# DIY_DAP_PCB_Audio.net
KiCad netlist of a schematic drawn in Altium Designer
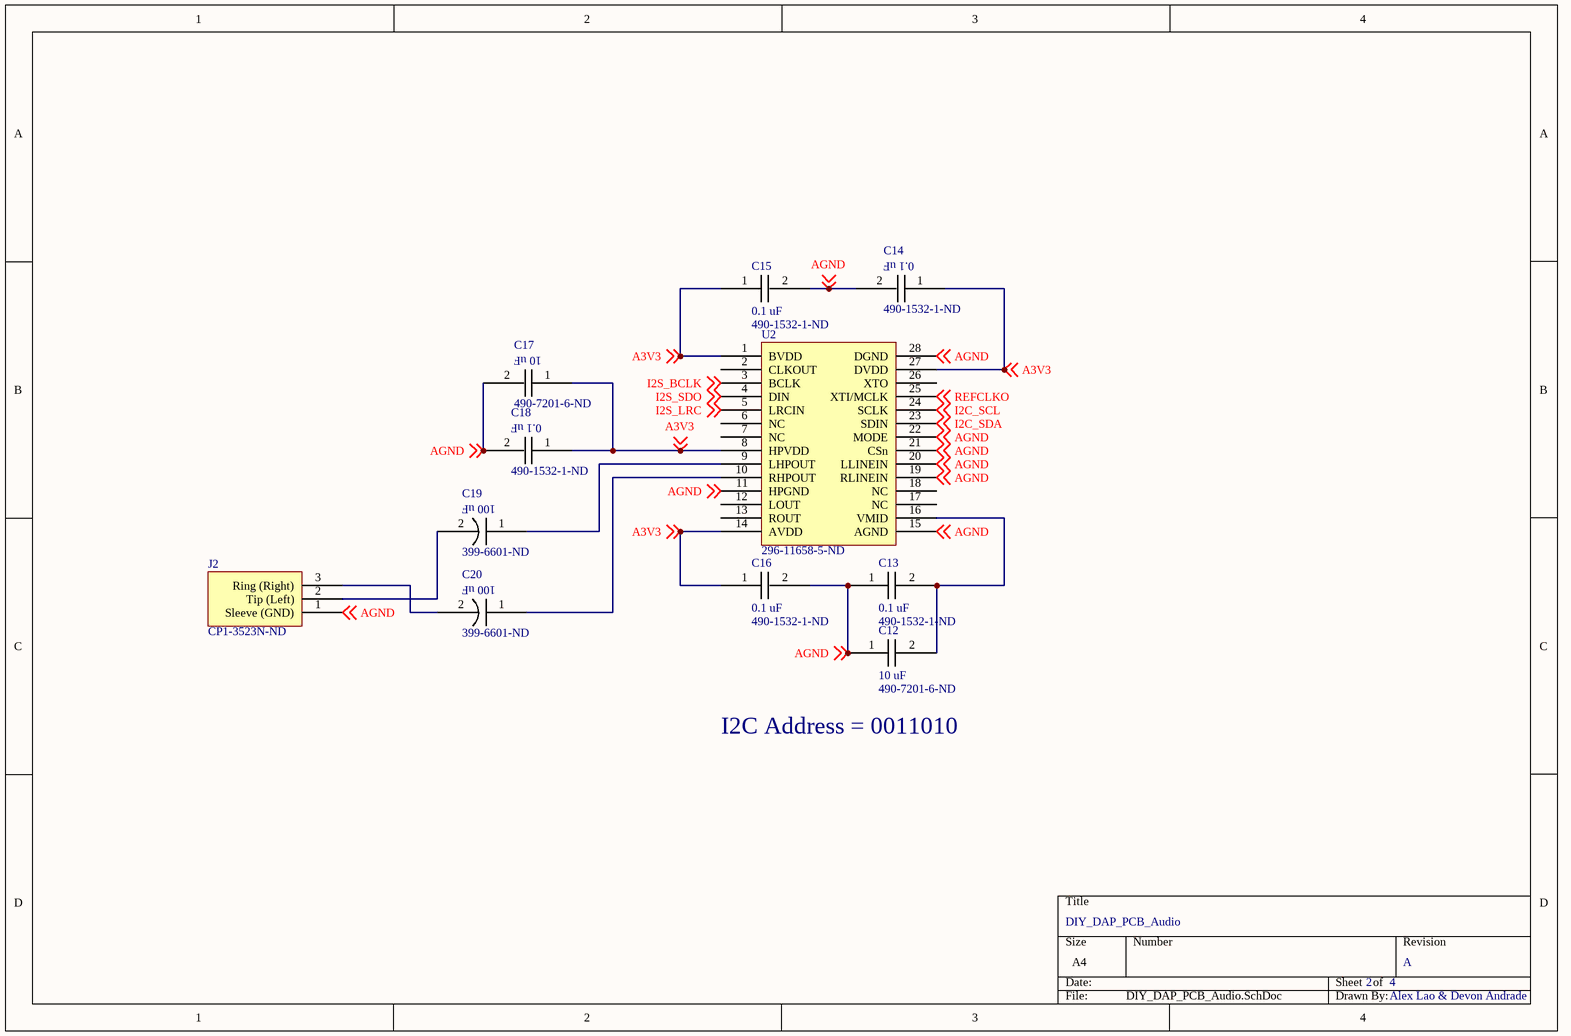
[diagram p0: DIY_DAP_PCB_Audio.SchDoc]

(export (version "E")
  (design (tool "Eeschema 10.0.6"))
  (components
    (comp (ref "C12")
      (value "490-7201-6-ND")
      (footprint "0603")
      (description "0603 10 uF - 16V - Ceramic Capacitor")
      (libsource (lib "DIY_DAP_PCB_Library") (part "490-7201-6-ND"))
    )
    (comp (ref "C13")
      (value "490-1532-1-ND")
      (footprint "0603")
      (description "0603 0.1 uF - 16V - Ceramic Capacitor")
      (libsource (lib "DIY_DAP_PCB_Library") (part "490-1532-1-ND"))
    )
    (comp (ref "C14")
      (value "490-1532-1-ND")
      (footprint "0603")
      (description "0603 0.1 uF - 16V - Ceramic Capacitor")
      (libsource (lib "DIY_DAP_PCB_Library") (part "490-1532-1-ND"))
    )
    (comp (ref "C15")
      (value "490-1532-1-ND")
      (footprint "0603")
      (description "0603 0.1 uF - 16V - Ceramic Capacitor")
      (libsource (lib "DIY_DAP_PCB_Library") (part "490-1532-1-ND"))
    )
    (comp (ref "C16")
      (value "490-1532-1-ND")
      (footprint "0603")
      (description "0603 0.1 uF - 16V - Ceramic Capacitor")
      (libsource (lib "DIY_DAP_PCB_Library") (part "490-1532-1-ND"))
    )
    (comp (ref "C17")
      (value "490-7201-6-ND")
      (footprint "0603")
      (description "0603 10 uF - 16V - Ceramic Capacitor")
      (libsource (lib "DIY_DAP_PCB_Library") (part "490-7201-6-ND"))
    )
    (comp (ref "C18")
      (value "490-1532-1-ND")
      (footprint "0603")
      (description "0603 0.1 uF - 16V - Ceramic Capacitor")
      (libsource (lib "DIY_DAP_PCB_Library") (part "490-1532-1-ND"))
    )
    (comp (ref "C19")
      (value "399-6601-ND")
      (footprint "399-6601-ND")
      (description "100 uF - 16V - Electrolytic Capacitor")
      (libsource (lib "DIY_DAP_PCB_Library") (part "399-6601-ND"))
    )
    (comp (ref "C20")
      (value "399-6601-ND")
      (footprint "399-6601-ND")
      (description "100 uF - 16V - Electrolytic Capacitor")
      (libsource (lib "DIY_DAP_PCB_Library") (part "399-6601-ND"))
    )
    (comp (ref "J2")
      (value "CP1-3523N-ND")
      (footprint "CP1-3523N-ND")
      (description "3.5mm Audio Jack")
      (libsource (lib "DIY_DAP_PCB_Library") (part "CP1-3523N-ND"))
    )
    (comp (ref "U2")
      (value "296-11658-5-ND")
      (footprint "296-11658-5-ND")
      (description "TLV320DAC23PW")
      (libsource (lib "DIY_DAP_PCB_Library") (part "296-11658-5-ND"))
    )
  )
  (nets
    (net (code "1") (name "A3V3") (class "Default")
      (node (ref "C14") (pin "1") (pinfunction "1_1") (pintype "passive"))
      (node (ref "C15") (pin "1") (pinfunction "1_1") (pintype "passive"))
      (node (ref "C16") (pin "1") (pinfunction "1_1") (pintype "passive"))
      (node (ref "C17") (pin "1") (pinfunction "1_1") (pintype "passive"))
      (node (ref "C18") (pin "1") (pinfunction "1_1") (pintype "passive"))
      (node (ref "U2") (pin "1") (pinfunction "BVDD_1") (pintype "passive"))
      (node (ref "U2") (pin "14") (pinfunction "AVDD_14") (pintype "passive"))
      (node (ref "U2") (pin "27") (pinfunction "DVDD_27") (pintype "passive"))
      (node (ref "U2") (pin "8") (pinfunction "HPVDD_8") (pintype "passive"))
    )
    (net (code "2") (name "AGND") (class "Default")
      (node (ref "C12") (pin "1") (pinfunction "1_1") (pintype "passive"))
      (node (ref "C13") (pin "1") (pinfunction "1_1") (pintype "passive"))
      (node (ref "C14") (pin "2") (pinfunction "2_2") (pintype "passive"))
      (node (ref "C15") (pin "2") (pinfunction "2_2") (pintype "passive"))
      (node (ref "C16") (pin "2") (pinfunction "2_2") (pintype "passive"))
      (node (ref "C17") (pin "2") (pinfunction "2_2") (pintype "passive"))
      (node (ref "C18") (pin "2") (pinfunction "2_2") (pintype "passive"))
      (node (ref "J2") (pin "1") (pinfunction "Sleeve_(GND)_1") (pintype "passive"))
      (node (ref "U2") (pin "11") (pinfunction "HPGND_11") (pintype "passive"))
      (node (ref "U2") (pin "15") (pinfunction "AGND_15") (pintype "passive"))
      (node (ref "U2") (pin "19") (pinfunction "RLINEIN_19") (pintype "passive"))
      (node (ref "U2") (pin "20") (pinfunction "LLINEIN_20") (pintype "passive"))
      (node (ref "U2") (pin "21") (pinfunction "CSn_21") (pintype "passive"))
      (node (ref "U2") (pin "22") (pinfunction "MODE_22") (pintype "passive"))
      (node (ref "U2") (pin "28") (pinfunction "DGND_28") (pintype "passive"))
    )
    (net (code "3") (name "I2C_SCL") (class "Default")
      (node (ref "U2") (pin "24") (pinfunction "SCLK_24") (pintype "passive"))
    )
    (net (code "4") (name "I2C_SDA") (class "Default")
      (node (ref "U2") (pin "23") (pinfunction "SDIN_23") (pintype "passive"))
    )
    (net (code "5") (name "I2S_BCLK") (class "Default")
      (node (ref "U2") (pin "3") (pinfunction "BCLK_3") (pintype "passive"))
    )
    (net (code "6") (name "I2S_LRC") (class "Default")
      (node (ref "U2") (pin "5") (pinfunction "LRCIN_5") (pintype "passive"))
    )
    (net (code "7") (name "I2S_SDO") (class "Default")
      (node (ref "U2") (pin "4") (pinfunction "DIN_4") (pintype "passive"))
    )
    (net (code "8") (name "Net-(J2-Ring_(Right))") (class "Default")
      (node (ref "C20") (pin "2") (pinfunction "2_2") (pintype "passive"))
      (node (ref "J2") (pin "3") (pinfunction "Ring_(Right)_3") (pintype "passive"))
    )
    (net (code "9") (name "Net-(J2-Tip_(Left))") (class "Default")
      (node (ref "C19") (pin "2") (pinfunction "2_2") (pintype "passive"))
      (node (ref "J2") (pin "2") (pinfunction "Tip_(Left)_2") (pintype "passive"))
    )
    (net (code "10") (name "Net-(U2-LHPOUT)") (class "Default")
      (node (ref "C19") (pin "1") (pinfunction "1_1") (pintype "passive"))
      (node (ref "U2") (pin "9") (pinfunction "LHPOUT_9") (pintype "passive"))
    )
    (net (code "11") (name "Net-(U2-RHPOUT)") (class "Default")
      (node (ref "C20") (pin "1") (pinfunction "1_1") (pintype "passive"))
      (node (ref "U2") (pin "10") (pinfunction "RHPOUT_10") (pintype "passive"))
    )
    (net (code "12") (name "Net-(U2-VMID)") (class "Default")
      (node (ref "C12") (pin "2") (pinfunction "2_2") (pintype "passive"))
      (node (ref "C13") (pin "2") (pinfunction "2_2") (pintype "passive"))
      (node (ref "U2") (pin "16") (pinfunction "VMID_16") (pintype "passive"))
    )
    (net (code "13") (name "REFCLKO") (class "Default")
      (node (ref "U2") (pin "25") (pinfunction "XTI/MCLK_25") (pintype "passive"))
    )
    (net (code "14") (name "unconnected-(U2-CLKOUT-Pad2)") (class "Default")
      (node (ref "U2") (pin "2") (pinfunction "CLKOUT_2") (pintype "passive"))
    )
    (net (code "15") (name "unconnected-(U2-LOUT-Pad12)") (class "Default")
      (node (ref "U2") (pin "12") (pinfunction "LOUT_12") (pintype "passive"))
    )
    (net (code "16") (name "unconnected-(U2-NC-Pad6)") (class "Default")
      (node (ref "U2") (pin "6") (pinfunction "NC_6") (pintype "passive"))
    )
    (net (code "17") (name "unconnected-(U2-NC-Pad7)") (class "Default")
      (node (ref "U2") (pin "7") (pinfunction "NC_7") (pintype "passive"))
    )
    (net (code "18") (name "unconnected-(U2-NC-Pad17)") (class "Default")
      (node (ref "U2") (pin "17") (pinfunction "NC_17") (pintype "passive"))
    )
    (net (code "19") (name "unconnected-(U2-NC-Pad18)") (class "Default")
      (node (ref "U2") (pin "18") (pinfunction "NC_18") (pintype "passive"))
    )
    (net (code "20") (name "unconnected-(U2-ROUT-Pad13)") (class "Default")
      (node (ref "U2") (pin "13") (pinfunction "ROUT_13") (pintype "passive"))
    )
    (net (code "21") (name "unconnected-(U2-XTO-Pad26)") (class "Default")
      (node (ref "U2") (pin "26") (pinfunction "XTO_26") (pintype "passive"))
    )
  )
)
